# ADCS2Umb.net
KiCad netlist of a schematic drawn in Altium Designer
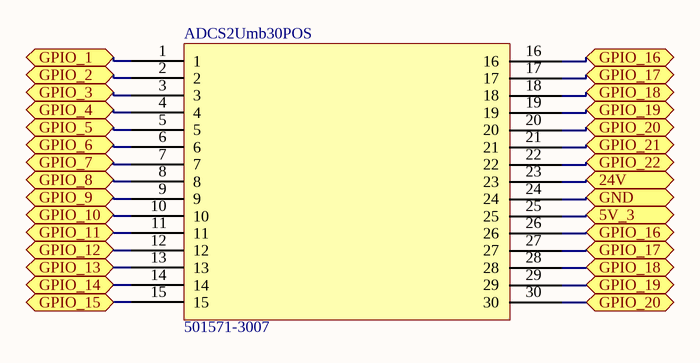
[diagram p0: ADCS2Umb.SchDoc]

(export (version "E")
  (design (tool "Eeschema 10.0.6"))
  (components
    (comp (ref "ADCS2Umb30POS")
      (value "501571-3007")
      (footprint "Docking_Molex_30Pin")
      (description "ADCS2Umb30POS")
      (libsource (lib "UmbilicalBoardV2") (part "501571-3007"))
    )
  )
  (nets
    (net (code "1") (name "/5V_3") (class "Default")
      (node (ref "ADCS2Umb30POS") (pin "25") (pinfunction "25_25") (pintype "passive"))
    )
    (net (code "2") (name "/24V") (class "Default")
      (node (ref "ADCS2Umb30POS") (pin "23") (pinfunction "23_23") (pintype "passive"))
    )
    (net (code "3") (name "/GND") (class "Default")
      (node (ref "ADCS2Umb30POS") (pin "24") (pinfunction "24_24") (pintype "passive"))
    )
    (net (code "4") (name "/GPIO_1") (class "Default")
      (node (ref "ADCS2Umb30POS") (pin "1") (pinfunction "1_1") (pintype "passive"))
    )
    (net (code "5") (name "/GPIO_2") (class "Default")
      (node (ref "ADCS2Umb30POS") (pin "2") (pinfunction "2_2") (pintype "passive"))
    )
    (net (code "6") (name "/GPIO_3") (class "Default")
      (node (ref "ADCS2Umb30POS") (pin "3") (pinfunction "3_3") (pintype "passive"))
    )
    (net (code "7") (name "/GPIO_4") (class "Default")
      (node (ref "ADCS2Umb30POS") (pin "4") (pinfunction "4_4") (pintype "passive"))
    )
    (net (code "8") (name "/GPIO_5") (class "Default")
      (node (ref "ADCS2Umb30POS") (pin "5") (pinfunction "5_5") (pintype "passive"))
    )
    (net (code "9") (name "/GPIO_6") (class "Default")
      (node (ref "ADCS2Umb30POS") (pin "6") (pinfunction "6_6") (pintype "passive"))
    )
    (net (code "10") (name "/GPIO_7") (class "Default")
      (node (ref "ADCS2Umb30POS") (pin "7") (pinfunction "7_7") (pintype "passive"))
    )
    (net (code "11") (name "/GPIO_8") (class "Default")
      (node (ref "ADCS2Umb30POS") (pin "8") (pinfunction "8_8") (pintype "passive"))
    )
    (net (code "12") (name "/GPIO_9") (class "Default")
      (node (ref "ADCS2Umb30POS") (pin "9") (pinfunction "9_9") (pintype "passive"))
    )
    (net (code "13") (name "/GPIO_10") (class "Default")
      (node (ref "ADCS2Umb30POS") (pin "10") (pinfunction "10_10") (pintype "passive"))
    )
    (net (code "14") (name "/GPIO_11") (class "Default")
      (node (ref "ADCS2Umb30POS") (pin "11") (pinfunction "11_11") (pintype "passive"))
    )
    (net (code "15") (name "/GPIO_12") (class "Default")
      (node (ref "ADCS2Umb30POS") (pin "12") (pinfunction "12_12") (pintype "passive"))
    )
    (net (code "16") (name "/GPIO_13") (class "Default")
      (node (ref "ADCS2Umb30POS") (pin "13") (pinfunction "13_13") (pintype "passive"))
    )
    (net (code "17") (name "/GPIO_14") (class "Default")
      (node (ref "ADCS2Umb30POS") (pin "14") (pinfunction "14_14") (pintype "passive"))
    )
    (net (code "18") (name "/GPIO_15") (class "Default")
      (node (ref "ADCS2Umb30POS") (pin "15") (pinfunction "15_15") (pintype "passive"))
    )
    (net (code "19") (name "/GPIO_16") (class "Default")
      (node (ref "ADCS2Umb30POS") (pin "16") (pinfunction "16_16") (pintype "passive"))
      (node (ref "ADCS2Umb30POS") (pin "26") (pinfunction "26_26") (pintype "passive"))
    )
    (net (code "20") (name "/GPIO_17") (class "Default")
      (node (ref "ADCS2Umb30POS") (pin "17") (pinfunction "17_17") (pintype "passive"))
      (node (ref "ADCS2Umb30POS") (pin "27") (pinfunction "27_27") (pintype "passive"))
    )
    (net (code "21") (name "/GPIO_18") (class "Default")
      (node (ref "ADCS2Umb30POS") (pin "18") (pinfunction "18_18") (pintype "passive"))
      (node (ref "ADCS2Umb30POS") (pin "28") (pinfunction "28_28") (pintype "passive"))
    )
    (net (code "22") (name "/GPIO_19") (class "Default")
      (node (ref "ADCS2Umb30POS") (pin "19") (pinfunction "19_19") (pintype "passive"))
      (node (ref "ADCS2Umb30POS") (pin "29") (pinfunction "29_29") (pintype "passive"))
    )
    (net (code "23") (name "/GPIO_20") (class "Default")
      (node (ref "ADCS2Umb30POS") (pin "20") (pinfunction "20_20") (pintype "passive"))
      (node (ref "ADCS2Umb30POS") (pin "30") (pinfunction "30_30") (pintype "passive"))
    )
    (net (code "24") (name "/GPIO_21") (class "Default")
      (node (ref "ADCS2Umb30POS") (pin "21") (pinfunction "21_21") (pintype "passive"))
    )
    (net (code "25") (name "/GPIO_22") (class "Default")
      (node (ref "ADCS2Umb30POS") (pin "22") (pinfunction "22_22") (pintype "passive"))
    )
  )
)
